# StepperSynth2_3_Motor.net
KiCad netlist of a schematic drawn in EAGLE
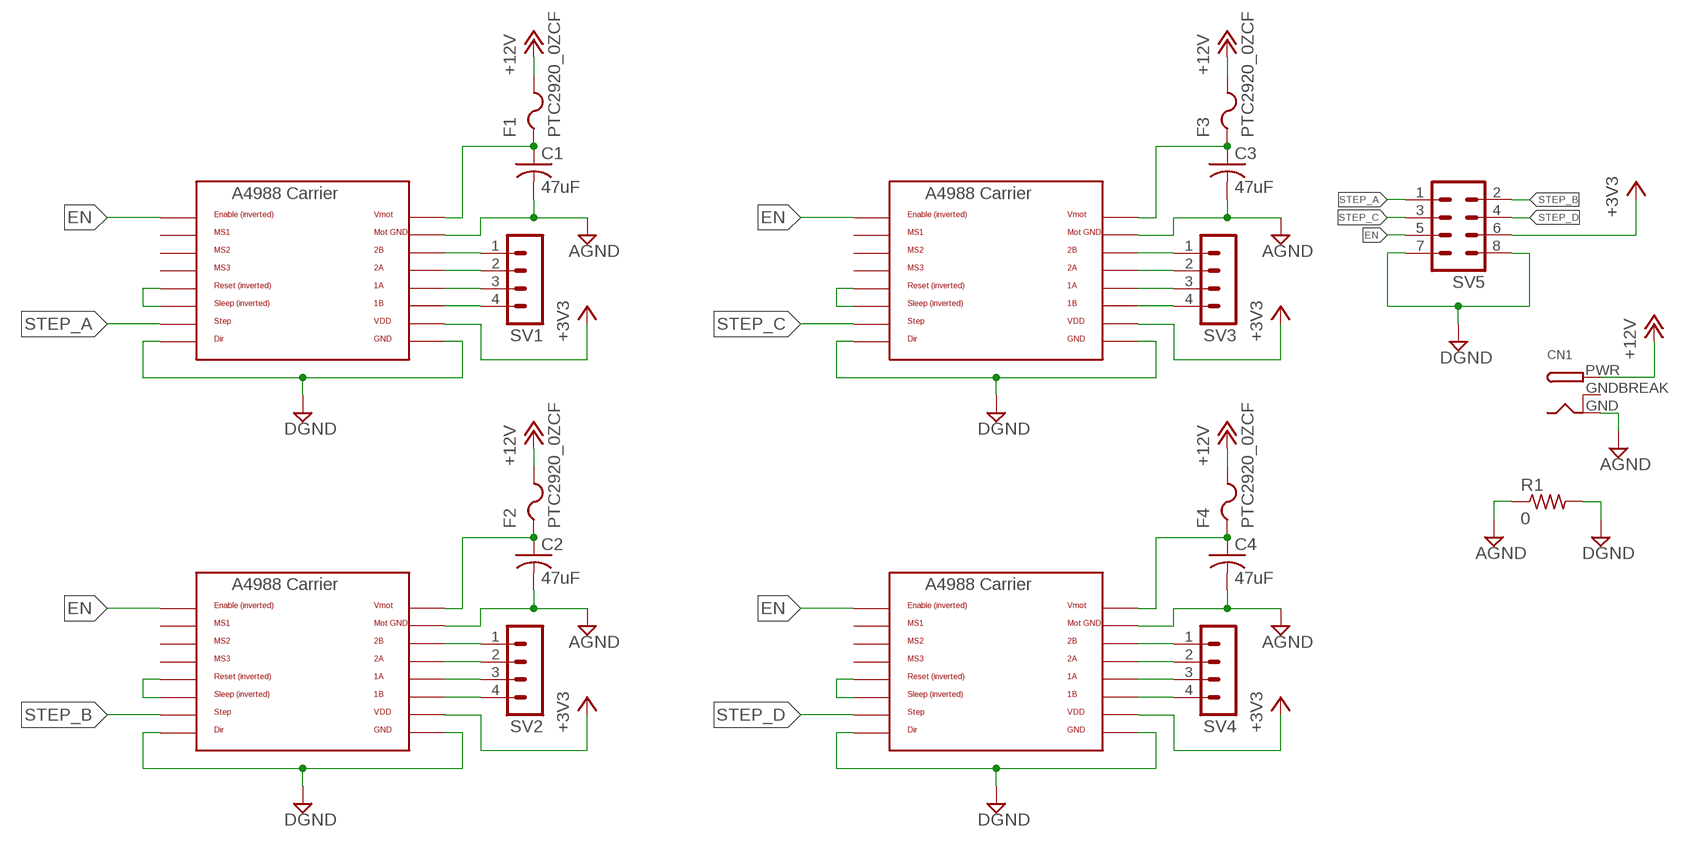
[diagram p0: schematic, sheet 1]

(export (version "E")
  (design (tool "Eeschema 10.0.6"))
  (components
    (comp (ref "C1")
      (value "47uF")
      (footprint "eagle-import:E5-10")
      (libsource (lib "eagle-import") (part "C_US_5_10"))
    )
    (comp (ref "C2")
      (value "47uF")
      (footprint "eagle-import:E5-10")
      (libsource (lib "eagle-import") (part "C_US_5_10"))
    )
    (comp (ref "C3")
      (value "47uF")
      (footprint "eagle-import:E5-10")
      (libsource (lib "eagle-import") (part "C_US_5_10"))
    )
    (comp (ref "C4")
      (value "47uF")
      (footprint "eagle-import:E5-10")
      (libsource (lib "eagle-import") (part "C_US_5_10"))
    )
    (comp (ref "CN1")
      (value "DCBARRELPTH")
      (footprint "eagle-import:DCJACK_2MM_PTH")
      (libsource (lib "eagle-import") (part "DCBARRELPTH"))
    )
    (comp (ref "F1")
      (value "PTC2920_0ZCF")
      (footprint "eagle-import:0ZCF")
      (fields (field (name "MANUFACTURER_PART_NUMBER") "0ZCF0150FF2C"))
      (libsource (lib "eagle-import") (part "PTC2920_0ZCF"))
    )
    (comp (ref "F2")
      (value "PTC2920_0ZCF")
      (footprint "eagle-import:0ZCF")
      (fields (field (name "MANUFACTURER_PART_NUMBER") "0ZCF0150FF2C"))
      (libsource (lib "eagle-import") (part "PTC2920_0ZCF"))
    )
    (comp (ref "F3")
      (value "PTC2920_0ZCF")
      (footprint "eagle-import:0ZCF")
      (fields (field (name "MANUFACTURER_PART_NUMBER") "0ZCF0150FF2C"))
      (libsource (lib "eagle-import") (part "PTC2920_0ZCF"))
    )
    (comp (ref "F4")
      (value "PTC2920_0ZCF")
      (footprint "eagle-import:0ZCF")
      (fields (field (name "MANUFACTURER_PART_NUMBER") "0ZCF0150FF2C"))
      (libsource (lib "eagle-import") (part "PTC2920_0ZCF"))
    )
    (comp (ref "R1")
      (value "0")
      (footprint "eagle-import:0204_5")
      (libsource (lib "eagle-import") (part "R-US_0204/5"))
    )
    (comp (ref "SV1")
      (value "MA04-1")
      (footprint "eagle-import:MA04-1")
      (libsource (lib "eagle-import") (part "MA04-1"))
    )
    (comp (ref "SV2")
      (value "MA04-1")
      (footprint "eagle-import:MA04-1")
      (libsource (lib "eagle-import") (part "MA04-1"))
    )
    (comp (ref "SV3")
      (value "MA04-1")
      (footprint "eagle-import:MA04-1")
      (libsource (lib "eagle-import") (part "MA04-1"))
    )
    (comp (ref "SV4")
      (value "MA04-1")
      (footprint "eagle-import:MA04-1")
      (libsource (lib "eagle-import") (part "MA04-1"))
    )
    (comp (ref "SV5")
      (value "MA04-2")
      (footprint "eagle-import:MA04-2")
      (libsource (lib "eagle-import") (part "MA04-2"))
    )
    (comp (ref "U$1")
      (value "A4988BREAKOUT")
      (footprint "eagle-import:A4988BREAKOUT")
      (libsource (lib "eagle-import") (part "A4988BREAKOUT"))
    )
    (comp (ref "U$2")
      (value "A4988BREAKOUT")
      (footprint "eagle-import:A4988BREAKOUT")
      (libsource (lib "eagle-import") (part "A4988BREAKOUT"))
    )
    (comp (ref "U$3")
      (value "A4988BREAKOUT")
      (footprint "eagle-import:A4988BREAKOUT")
      (libsource (lib "eagle-import") (part "A4988BREAKOUT"))
    )
    (comp (ref "U$4")
      (value "A4988BREAKOUT")
      (footprint "eagle-import:A4988BREAKOUT")
      (libsource (lib "eagle-import") (part "A4988BREAKOUT"))
    )
  )
  (nets
    (net (code "1") (name "+3V3") (class "Default")
      (node (ref "SV5") (pin "6") (pinfunction "6_6") (pintype "passive"))
      (node (ref "U$1") (pin "VDD") (pinfunction "VDD_VDD") (pintype "power_in"))
      (node (ref "U$2") (pin "VDD") (pinfunction "VDD_VDD") (pintype "power_in"))
      (node (ref "U$3") (pin "VDD") (pinfunction "VDD_VDD") (pintype "power_in"))
      (node (ref "U$4") (pin "VDD") (pinfunction "VDD_VDD") (pintype "power_in"))
    )
    (net (code "2") (name "+12V") (class "Default")
      (node (ref "CN1") (pin "PWR") (pinfunction "PWR_PWR") (pintype "power_in"))
      (node (ref "F1") (pin "2") (pinfunction "2_2") (pintype "passive"))
      (node (ref "F2") (pin "2") (pinfunction "2_2") (pintype "passive"))
      (node (ref "F3") (pin "2") (pinfunction "2_2") (pintype "passive"))
      (node (ref "F4") (pin "2") (pinfunction "2_2") (pintype "passive"))
    )
    (net (code "3") (name "/GNDBREAK") (class "Default")
      (node (ref "CN1") (pin "GNDBREAK") (pinfunction "GNDBREAK_GNDBREAK") (pintype "power_in"))
    )
    (net (code "4") (name "AGND") (class "Default")
      (node (ref "C1") (pin "-") (pinfunction "-_-") (pintype "passive"))
      (node (ref "C2") (pin "-") (pinfunction "-_-") (pintype "passive"))
      (node (ref "C3") (pin "-") (pinfunction "-_-") (pintype "passive"))
      (node (ref "C4") (pin "-") (pinfunction "-_-") (pintype "passive"))
      (node (ref "CN1") (pin "GND") (pinfunction "GND_GND") (pintype "power_in"))
      (node (ref "R1") (pin "1") (pinfunction "1_1") (pintype "passive"))
      (node (ref "U$1") (pin "MOTGND") (pinfunction "MOTGND_MOTGND") (pintype "power_in"))
      (node (ref "U$2") (pin "MOTGND") (pinfunction "MOTGND_MOTGND") (pintype "power_in"))
      (node (ref "U$3") (pin "MOTGND") (pinfunction "MOTGND_MOTGND") (pintype "power_in"))
      (node (ref "U$4") (pin "MOTGND") (pinfunction "MOTGND_MOTGND") (pintype "power_in"))
    )
    (net (code "5") (name "DGND") (class "Default")
      (node (ref "R1") (pin "2") (pinfunction "2_2") (pintype "passive"))
      (node (ref "SV5") (pin "7") (pinfunction "7_7") (pintype "passive"))
      (node (ref "SV5") (pin "8") (pinfunction "8_8") (pintype "passive"))
      (node (ref "U$1") (pin "DIR") (pinfunction "DIR_DIR") (pintype "input"))
      (node (ref "U$1") (pin "GND") (pinfunction "GND_GND") (pintype "power_in"))
      (node (ref "U$2") (pin "DIR") (pinfunction "DIR_DIR") (pintype "input"))
      (node (ref "U$2") (pin "GND") (pinfunction "GND_GND") (pintype "power_in"))
      (node (ref "U$3") (pin "DIR") (pinfunction "DIR_DIR") (pintype "input"))
      (node (ref "U$3") (pin "GND") (pinfunction "GND_GND") (pintype "power_in"))
      (node (ref "U$4") (pin "DIR") (pinfunction "DIR_DIR") (pintype "input"))
      (node (ref "U$4") (pin "GND") (pinfunction "GND_GND") (pintype "power_in"))
    )
    (net (code "6") (name "EN") (class "Default")
      (node (ref "SV5") (pin "5") (pinfunction "5_5") (pintype "passive"))
      (node (ref "U$1") (pin "EN") (pinfunction "EN_EN") (pintype "input"))
      (node (ref "U$2") (pin "EN") (pinfunction "EN_EN") (pintype "input"))
      (node (ref "U$3") (pin "EN") (pinfunction "EN_EN") (pintype "input"))
      (node (ref "U$4") (pin "EN") (pinfunction "EN_EN") (pintype "input"))
    )
    (net (code "7") (name "Net-(C1-Pad+)") (class "Default")
      (node (ref "C1") (pin "+") (pinfunction "+_+") (pintype "passive"))
      (node (ref "F1") (pin "1") (pinfunction "1_1") (pintype "passive"))
      (node (ref "U$1") (pin "VMOT") (pinfunction "VMOT_VMOT") (pintype "power_in"))
    )
    (net (code "8") (name "Net-(C2-Pad+)") (class "Default")
      (node (ref "C2") (pin "+") (pinfunction "+_+") (pintype "passive"))
      (node (ref "F2") (pin "1") (pinfunction "1_1") (pintype "passive"))
      (node (ref "U$2") (pin "VMOT") (pinfunction "VMOT_VMOT") (pintype "power_in"))
    )
    (net (code "9") (name "Net-(C3-Pad+)") (class "Default")
      (node (ref "C3") (pin "+") (pinfunction "+_+") (pintype "passive"))
      (node (ref "F3") (pin "1") (pinfunction "1_1") (pintype "passive"))
      (node (ref "U$3") (pin "VMOT") (pinfunction "VMOT_VMOT") (pintype "power_in"))
    )
    (net (code "10") (name "Net-(C4-Pad+)") (class "Default")
      (node (ref "C4") (pin "+") (pinfunction "+_+") (pintype "passive"))
      (node (ref "F4") (pin "1") (pinfunction "1_1") (pintype "passive"))
      (node (ref "U$4") (pin "VMOT") (pinfunction "VMOT_VMOT") (pintype "power_in"))
    )
    (net (code "11") (name "Net-(SV1-Pad1)") (class "Default")
      (node (ref "SV1") (pin "1") (pinfunction "1_1") (pintype "passive"))
      (node (ref "U$1") (pin "2B") (pinfunction "2B_2B") (pintype "output"))
    )
    (net (code "12") (name "Net-(SV1-Pad2)") (class "Default")
      (node (ref "SV1") (pin "2") (pinfunction "2_2") (pintype "passive"))
      (node (ref "U$1") (pin "2A") (pinfunction "2A_2A") (pintype "output"))
    )
    (net (code "13") (name "Net-(SV1-Pad3)") (class "Default")
      (node (ref "SV1") (pin "3") (pinfunction "3_3") (pintype "passive"))
      (node (ref "U$1") (pin "1A") (pinfunction "1A_1A") (pintype "output"))
    )
    (net (code "14") (name "Net-(SV1-Pad4)") (class "Default")
      (node (ref "SV1") (pin "4") (pinfunction "4_4") (pintype "passive"))
      (node (ref "U$1") (pin "1B") (pinfunction "1B_1B") (pintype "output"))
    )
    (net (code "15") (name "Net-(SV2-Pad1)") (class "Default")
      (node (ref "SV2") (pin "1") (pinfunction "1_1") (pintype "passive"))
      (node (ref "U$2") (pin "2B") (pinfunction "2B_2B") (pintype "output"))
    )
    (net (code "16") (name "Net-(SV2-Pad2)") (class "Default")
      (node (ref "SV2") (pin "2") (pinfunction "2_2") (pintype "passive"))
      (node (ref "U$2") (pin "2A") (pinfunction "2A_2A") (pintype "output"))
    )
    (net (code "17") (name "Net-(SV2-Pad3)") (class "Default")
      (node (ref "SV2") (pin "3") (pinfunction "3_3") (pintype "passive"))
      (node (ref "U$2") (pin "1A") (pinfunction "1A_1A") (pintype "output"))
    )
    (net (code "18") (name "Net-(SV2-Pad4)") (class "Default")
      (node (ref "SV2") (pin "4") (pinfunction "4_4") (pintype "passive"))
      (node (ref "U$2") (pin "1B") (pinfunction "1B_1B") (pintype "output"))
    )
    (net (code "19") (name "Net-(SV3-Pad1)") (class "Default")
      (node (ref "SV3") (pin "1") (pinfunction "1_1") (pintype "passive"))
      (node (ref "U$3") (pin "2B") (pinfunction "2B_2B") (pintype "output"))
    )
    (net (code "20") (name "Net-(SV3-Pad2)") (class "Default")
      (node (ref "SV3") (pin "2") (pinfunction "2_2") (pintype "passive"))
      (node (ref "U$3") (pin "2A") (pinfunction "2A_2A") (pintype "output"))
    )
    (net (code "21") (name "Net-(SV3-Pad3)") (class "Default")
      (node (ref "SV3") (pin "3") (pinfunction "3_3") (pintype "passive"))
      (node (ref "U$3") (pin "1A") (pinfunction "1A_1A") (pintype "output"))
    )
    (net (code "22") (name "Net-(SV3-Pad4)") (class "Default")
      (node (ref "SV3") (pin "4") (pinfunction "4_4") (pintype "passive"))
      (node (ref "U$3") (pin "1B") (pinfunction "1B_1B") (pintype "output"))
    )
    (net (code "23") (name "Net-(SV4-Pad1)") (class "Default")
      (node (ref "SV4") (pin "1") (pinfunction "1_1") (pintype "passive"))
      (node (ref "U$4") (pin "2B") (pinfunction "2B_2B") (pintype "output"))
    )
    (net (code "24") (name "Net-(SV4-Pad2)") (class "Default")
      (node (ref "SV4") (pin "2") (pinfunction "2_2") (pintype "passive"))
      (node (ref "U$4") (pin "2A") (pinfunction "2A_2A") (pintype "output"))
    )
    (net (code "25") (name "Net-(SV4-Pad3)") (class "Default")
      (node (ref "SV4") (pin "3") (pinfunction "3_3") (pintype "passive"))
      (node (ref "U$4") (pin "1A") (pinfunction "1A_1A") (pintype "output"))
    )
    (net (code "26") (name "Net-(SV4-Pad4)") (class "Default")
      (node (ref "SV4") (pin "4") (pinfunction "4_4") (pintype "passive"))
      (node (ref "U$4") (pin "1B") (pinfunction "1B_1B") (pintype "output"))
    )
    (net (code "27") (name "Net-(U$1-SLEEP)") (class "Default")
      (node (ref "U$1") (pin "RST") (pinfunction "RST_RST") (pintype "input"))
      (node (ref "U$1") (pin "SLP") (pinfunction "SLEEP_SLP") (pintype "input"))
    )
    (net (code "28") (name "Net-(U$2-SLEEP)") (class "Default")
      (node (ref "U$2") (pin "RST") (pinfunction "RST_RST") (pintype "input"))
      (node (ref "U$2") (pin "SLP") (pinfunction "SLEEP_SLP") (pintype "input"))
    )
    (net (code "29") (name "Net-(U$3-SLEEP)") (class "Default")
      (node (ref "U$3") (pin "RST") (pinfunction "RST_RST") (pintype "input"))
      (node (ref "U$3") (pin "SLP") (pinfunction "SLEEP_SLP") (pintype "input"))
    )
    (net (code "30") (name "Net-(U$4-SLEEP)") (class "Default")
      (node (ref "U$4") (pin "RST") (pinfunction "RST_RST") (pintype "input"))
      (node (ref "U$4") (pin "SLP") (pinfunction "SLEEP_SLP") (pintype "input"))
    )
    (net (code "31") (name "STEP_A") (class "Default")
      (node (ref "SV5") (pin "1") (pinfunction "1_1") (pintype "passive"))
      (node (ref "U$1") (pin "STEP") (pinfunction "STEP_STEP") (pintype "input"))
    )
    (net (code "32") (name "STEP_B") (class "Default")
      (node (ref "SV5") (pin "2") (pinfunction "2_2") (pintype "passive"))
      (node (ref "U$2") (pin "STEP") (pinfunction "STEP_STEP") (pintype "input"))
    )
    (net (code "33") (name "STEP_C") (class "Default")
      (node (ref "SV5") (pin "3") (pinfunction "3_3") (pintype "passive"))
      (node (ref "U$3") (pin "STEP") (pinfunction "STEP_STEP") (pintype "input"))
    )
    (net (code "34") (name "STEP_D") (class "Default")
      (node (ref "SV5") (pin "4") (pinfunction "4_4") (pintype "passive"))
      (node (ref "U$4") (pin "STEP") (pinfunction "STEP_STEP") (pintype "input"))
    )
    (net (code "35") (name "unconnected-(U$1-PadMS1)") (class "Default")
      (node (ref "U$1") (pin "MS1") (pinfunction "MS1_MS1") (pintype "input"))
    )
    (net (code "36") (name "unconnected-(U$1-PadMS2)") (class "Default")
      (node (ref "U$1") (pin "MS2") (pinfunction "MS2_MS2") (pintype "input"))
    )
    (net (code "37") (name "unconnected-(U$1-PadMS3)") (class "Default")
      (node (ref "U$1") (pin "MS3") (pinfunction "MS3_MS3") (pintype "input"))
    )
    (net (code "38") (name "unconnected-(U$2-PadMS1)") (class "Default")
      (node (ref "U$2") (pin "MS1") (pinfunction "MS1_MS1") (pintype "input"))
    )
    (net (code "39") (name "unconnected-(U$2-PadMS2)") (class "Default")
      (node (ref "U$2") (pin "MS2") (pinfunction "MS2_MS2") (pintype "input"))
    )
    (net (code "40") (name "unconnected-(U$2-PadMS3)") (class "Default")
      (node (ref "U$2") (pin "MS3") (pinfunction "MS3_MS3") (pintype "input"))
    )
    (net (code "41") (name "unconnected-(U$3-PadMS1)") (class "Default")
      (node (ref "U$3") (pin "MS1") (pinfunction "MS1_MS1") (pintype "input"))
    )
    (net (code "42") (name "unconnected-(U$3-PadMS2)") (class "Default")
      (node (ref "U$3") (pin "MS2") (pinfunction "MS2_MS2") (pintype "input"))
    )
    (net (code "43") (name "unconnected-(U$3-PadMS3)") (class "Default")
      (node (ref "U$3") (pin "MS3") (pinfunction "MS3_MS3") (pintype "input"))
    )
    (net (code "44") (name "unconnected-(U$4-PadMS1)") (class "Default")
      (node (ref "U$4") (pin "MS1") (pinfunction "MS1_MS1") (pintype "input"))
    )
    (net (code "45") (name "unconnected-(U$4-PadMS2)") (class "Default")
      (node (ref "U$4") (pin "MS2") (pinfunction "MS2_MS2") (pintype "input"))
    )
    (net (code "46") (name "unconnected-(U$4-PadMS3)") (class "Default")
      (node (ref "U$4") (pin "MS3") (pinfunction "MS3_MS3") (pintype "input"))
    )
  )
)
